# lights.net
KiCad netlist of a schematic drawn in Altium Designer
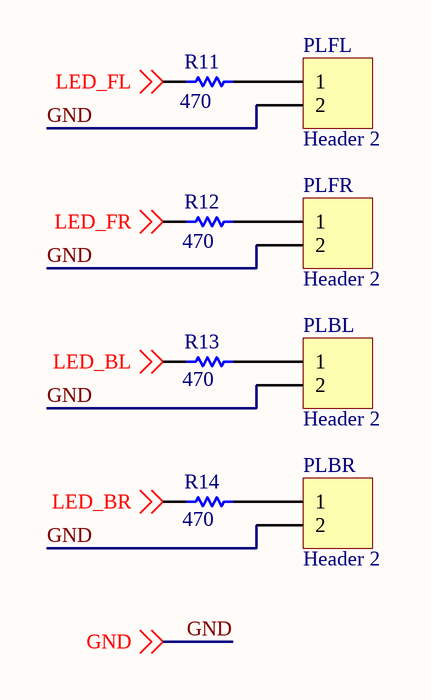
[diagram p0: lights.SchDoc]

(export (version "E")
  (design (tool "Eeschema 10.0.6"))
  (components
    (comp (ref "PLBL")
      (value "Header 2")
      (footprint "HDR1X2")
      (description "Header, 2-Pin")
      (fields (field (name "PUBLISHER") "Altium Limited"))
      (libsource (lib "Miscellaneous Connectors") (part "Header 2"))
    )
    (comp (ref "PLBR")
      (value "Header 2")
      (footprint "HDR1X2")
      (description "Header, 2-Pin")
      (fields (field (name "PUBLISHER") "Altium Limited"))
      (libsource (lib "Miscellaneous Connectors") (part "Header 2"))
    )
    (comp (ref "PLFL")
      (value "Header 2")
      (footprint "HDR1X2")
      (description "Header, 2-Pin")
      (fields (field (name "PUBLISHER") "Altium Limited"))
      (libsource (lib "Miscellaneous Connectors") (part "Header 2"))
    )
    (comp (ref "PLFR")
      (value "Header 2")
      (footprint "HDR1X2")
      (description "Header, 2-Pin")
      (fields (field (name "PUBLISHER") "Altium Limited"))
      (libsource (lib "Miscellaneous Connectors") (part "Header 2"))
    )
    (comp (ref "R11")
      (value "470")
      (footprint "0805-R")
      (description "Resistor")
      (fields (field (name "Comment") "Res1") (field (name "PUBLISHER") "Altium Limited"))
      (libsource (lib "Miscellaneous Devices") (part "Res1"))
    )
    (comp (ref "R12")
      (value "470")
      (footprint "0805-R")
      (description "Resistor")
      (fields (field (name "Comment") "Res1") (field (name "PUBLISHER") "Altium Limited"))
      (libsource (lib "Miscellaneous Devices") (part "Res1"))
    )
    (comp (ref "R13")
      (value "470")
      (footprint "0805-R")
      (description "Resistor")
      (fields (field (name "Comment") "Res1") (field (name "PUBLISHER") "Altium Limited"))
      (libsource (lib "Miscellaneous Devices") (part "Res1"))
    )
    (comp (ref "R14")
      (value "470")
      (footprint "0805-R")
      (description "Resistor")
      (fields (field (name "Comment") "Res1") (field (name "PUBLISHER") "Altium Limited"))
      (libsource (lib "Miscellaneous Devices") (part "Res1"))
    )
  )
  (nets
    (net (code "1") (name "GND") (class "Default")
      (node (ref "PLBL") (pin "2") (pinfunction "2_2") (pintype "passive"))
      (node (ref "PLBR") (pin "2") (pinfunction "2_2") (pintype "passive"))
      (node (ref "PLFL") (pin "2") (pinfunction "2_2") (pintype "passive"))
      (node (ref "PLFR") (pin "2") (pinfunction "2_2") (pintype "passive"))
    )
    (net (code "2") (name "LED_BL") (class "Default")
      (node (ref "R13") (pin "1") (pinfunction "1_1") (pintype "passive"))
    )
    (net (code "3") (name "LED_BR") (class "Default")
      (node (ref "R14") (pin "1") (pinfunction "1_1") (pintype "passive"))
    )
    (net (code "4") (name "LED_FL") (class "Default")
      (node (ref "R11") (pin "1") (pinfunction "1_1") (pintype "passive"))
    )
    (net (code "5") (name "LED_FR") (class "Default")
      (node (ref "R12") (pin "1") (pinfunction "1_1") (pintype "passive"))
    )
    (net (code "6") (name "Net-(PLBL-Pad1)") (class "Default")
      (node (ref "PLBL") (pin "1") (pinfunction "1_1") (pintype "passive"))
      (node (ref "R13") (pin "2") (pinfunction "2_2") (pintype "passive"))
    )
    (net (code "7") (name "Net-(PLBR-Pad1)") (class "Default")
      (node (ref "PLBR") (pin "1") (pinfunction "1_1") (pintype "passive"))
      (node (ref "R14") (pin "2") (pinfunction "2_2") (pintype "passive"))
    )
    (net (code "8") (name "Net-(PLFL-Pad1)") (class "Default")
      (node (ref "PLFL") (pin "1") (pinfunction "1_1") (pintype "passive"))
      (node (ref "R11") (pin "2") (pinfunction "2_2") (pintype "passive"))
    )
    (net (code "9") (name "Net-(PLFR-Pad1)") (class "Default")
      (node (ref "PLFR") (pin "1") (pinfunction "1_1") (pintype "passive"))
      (node (ref "R12") (pin "2") (pinfunction "2_2") (pintype "passive"))
    )
  )
)
